# Halleffektsgivare_kort.net
KiCad netlist of a schematic drawn in Altium Designer
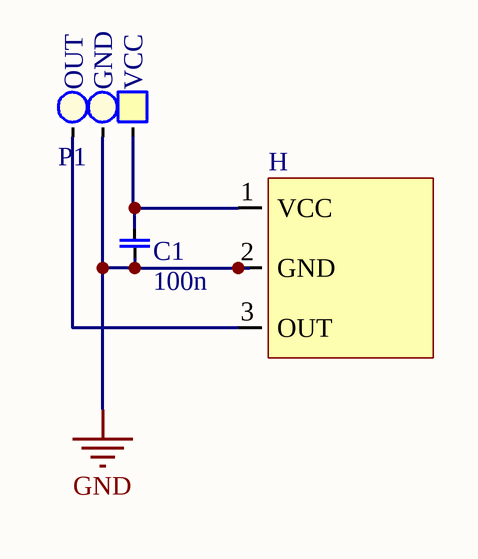
[diagram p0: Halleffektsgivare_kort.SchDoc]

(export (version "E")
  (design (tool "Eeschema 10.0.6"))
  (components
    (comp (ref "C1")
      (value "100n")
      (footprint "0402 CAP")
      (fields (field (name "Comment") "0402 capacitor"))
      (libsource (lib "jclib") (part "0402 capacitor"))
    )
    (comp (ref "H")
      (value "~")
      (footprint "Allegro A1324")
      (description "ALLEGRO A1324, SIP-3")
      (libsource (lib "jclib") (part "ALLEGRO A1324"))
    )
    (comp (ref "P1")
      (value "1x3 Pin Header")
      (footprint "padThree_L")
      (description "2.54 mm")
      (libsource (lib "jclib") (part "1x3 Pin Header"))
    )
  )
  (nets
    (net (code "1") (name "GND") (class "Default")
      (node (ref "C1") (pin "1") (pinfunction "1_1") (pintype "passive"))
      (node (ref "H") (pin "2") (pinfunction "GND_2") (pintype "passive"))
      (node (ref "P1") (pin "2") (pinfunction "2_2") (pintype "passive"))
    )
    (net (code "2") (name "Net-(H-OUT)") (class "Default")
      (node (ref "H") (pin "3") (pinfunction "OUT_3") (pintype "passive"))
      (node (ref "P1") (pin "3") (pinfunction "3_3") (pintype "passive"))
    )
    (net (code "3") (name "Net-(H-VCC)") (class "Default")
      (node (ref "C1") (pin "2") (pinfunction "2_2") (pintype "passive"))
      (node (ref "H") (pin "1") (pinfunction "VCC_1") (pintype "passive"))
      (node (ref "P1") (pin "1") (pinfunction "1_1") (pintype "passive"))
    )
  )
)
